# Switch.net
KiCad netlist of a schematic drawn in EAGLE
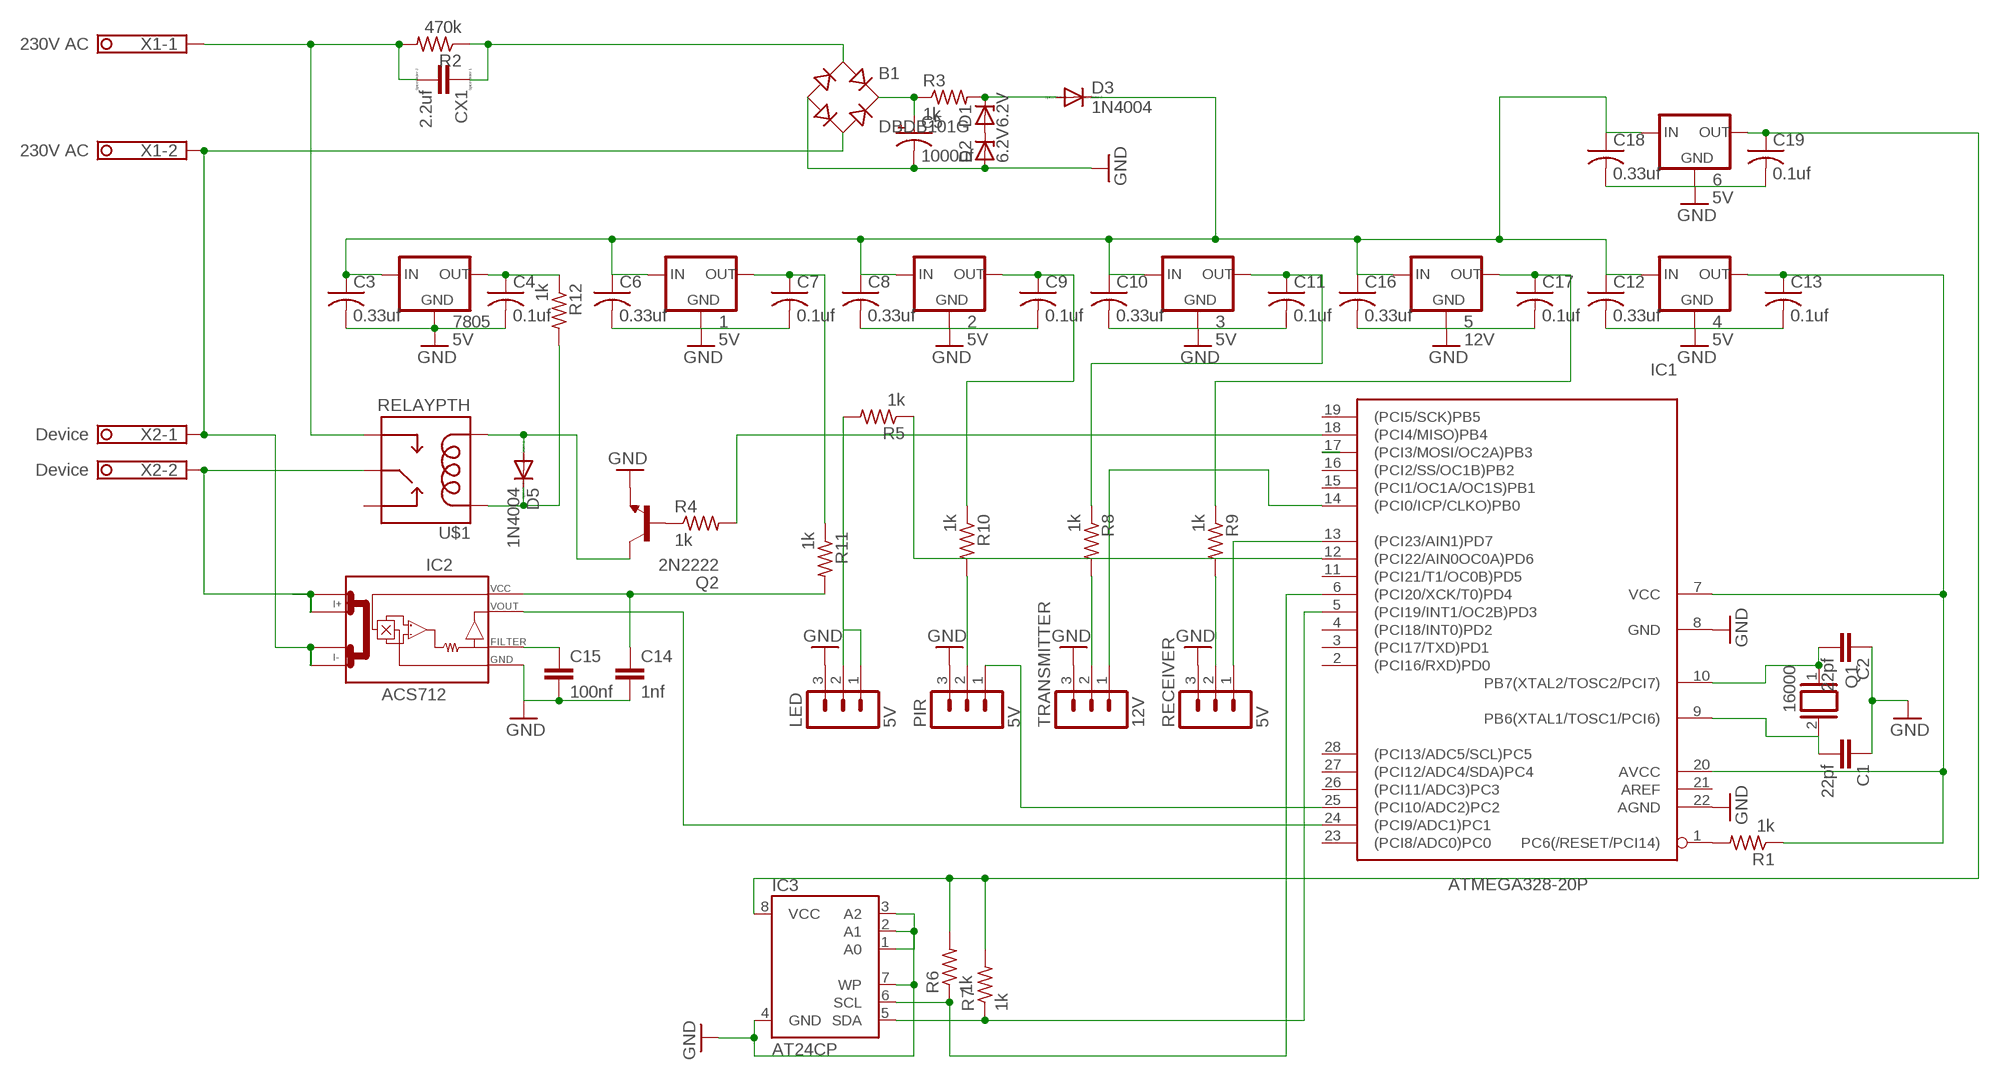
[diagram p0: schematic, sheet 1]

(export (version "E")
  (design (tool "Eeschema 10.0.6"))
  (components
    (comp (ref "1")
      (value "5V")
      (footprint "eagle-import:78XXL")
      (libsource (lib "eagle-import") (part "78XXL"))
    )
    (comp (ref "2")
      (value "5V")
      (footprint "eagle-import:78XXL")
      (libsource (lib "eagle-import") (part "78XXL"))
    )
    (comp (ref "3")
      (value "5V")
      (footprint "eagle-import:78XXL")
      (libsource (lib "eagle-import") (part "78XXL"))
    )
    (comp (ref "4")
      (value "5V")
      (footprint "eagle-import:78XXL")
      (libsource (lib "eagle-import") (part "78XXL"))
    )
    (comp (ref "5")
      (value "12V")
      (footprint "eagle-import:78XXL")
      (libsource (lib "eagle-import") (part "78XXL"))
    )
    (comp (ref "6")
      (value "5V")
      (footprint "eagle-import:78XXL")
      (libsource (lib "eagle-import") (part "78XXL"))
    )
    (comp (ref "7805")
      (value "5V")
      (footprint "eagle-import:78XXL")
      (libsource (lib "eagle-import") (part "78XXL"))
    )
    (comp (ref "B1")
      (value "DBDB101G")
      (footprint "eagle-import:DB")
      (libsource (lib "eagle-import") (part "DB?GDB101"))
    )
    (comp (ref "C1")
      (value "22pf")
      (footprint "eagle-import:C050-030X075")
      (libsource (lib "eagle-import") (part "C-EU050-030X075"))
    )
    (comp (ref "C2")
      (value "22pf")
      (footprint "eagle-import:C050-030X075")
      (libsource (lib "eagle-import") (part "C-EU050-030X075"))
    )
    (comp (ref "C3")
      (value "0.33uf")
      (footprint "eagle-import:C025-024X044")
      (libsource (lib "eagle-import") (part "C-US025-024X044"))
    )
    (comp (ref "C4")
      (value "0.1uf")
      (footprint "eagle-import:C025-024X044")
      (libsource (lib "eagle-import") (part "C-US025-024X044"))
    )
    (comp (ref "C5")
      (value "1000uf")
      (footprint "eagle-import:E2,5-7")
      (libsource (lib "eagle-import") (part "CPOL-USE2.5-7"))
    )
    (comp (ref "C6")
      (value "0.33uf")
      (footprint "eagle-import:C025-024X044")
      (libsource (lib "eagle-import") (part "C-US025-024X044"))
    )
    (comp (ref "C7")
      (value "0.1uf")
      (footprint "eagle-import:C025-024X044")
      (libsource (lib "eagle-import") (part "C-US025-024X044"))
    )
    (comp (ref "C8")
      (value "0.33uf")
      (footprint "eagle-import:C025-024X044")
      (libsource (lib "eagle-import") (part "C-US025-024X044"))
    )
    (comp (ref "C9")
      (value "0.1uf")
      (footprint "eagle-import:C025-024X044")
      (libsource (lib "eagle-import") (part "C-US025-024X044"))
    )
    (comp (ref "C10")
      (value "0.33uf")
      (footprint "eagle-import:C025-024X044")
      (libsource (lib "eagle-import") (part "C-US025-024X044"))
    )
    (comp (ref "C11")
      (value "0.1uf")
      (footprint "eagle-import:C025-024X044")
      (libsource (lib "eagle-import") (part "C-US025-024X044"))
    )
    (comp (ref "C12")
      (value "0.33uf")
      (footprint "eagle-import:C025-024X044")
      (libsource (lib "eagle-import") (part "C-US025-024X044"))
    )
    (comp (ref "C13")
      (value "0.1uf")
      (footprint "eagle-import:C025-024X044")
      (libsource (lib "eagle-import") (part "C-US025-024X044"))
    )
    (comp (ref "C14")
      (value "1nf")
      (footprint "eagle-import:C050-025X075")
      (libsource (lib "eagle-import") (part "C-EU050-025X075"))
    )
    (comp (ref "C15")
      (value "100nf")
      (footprint "eagle-import:C050-024X044")
      (libsource (lib "eagle-import") (part "C-EU050-024X044"))
    )
    (comp (ref "C16")
      (value "0.33uf")
      (footprint "eagle-import:C025-024X044")
      (libsource (lib "eagle-import") (part "C-US025-024X044"))
    )
    (comp (ref "C17")
      (value "0.1uf")
      (footprint "eagle-import:C025-024X044")
      (libsource (lib "eagle-import") (part "C-US025-024X044"))
    )
    (comp (ref "C18")
      (value "0.33uf")
      (footprint "eagle-import:C025-024X044")
      (libsource (lib "eagle-import") (part "C-US025-024X044"))
    )
    (comp (ref "C19")
      (value "0.1uf")
      (footprint "eagle-import:C025-024X044")
      (libsource (lib "eagle-import") (part "C-US025-024X044"))
    )
    (comp (ref "CX1")
      (value "2.2uf")
      (footprint "eagle-import:XC15B6")
      (libsource (lib "eagle-import") (part "CXXC15B6"))
    )
    (comp (ref "D1")
      (value "6.2V")
      (footprint "eagle-import:DO35Z10")
      (libsource (lib "eagle-import") (part "ZENER-DIODEDO35Z10"))
    )
    (comp (ref "D2")
      (value "6.2V")
      (footprint "eagle-import:DO35Z10")
      (libsource (lib "eagle-import") (part "ZENER-DIODEDO35Z10"))
    )
    (comp (ref "D3")
      (value "1N4004")
      (footprint "eagle-import:DO41-10")
      (libsource (lib "eagle-import") (part "1N4004"))
    )
    (comp (ref "D5")
      (value "1N4004")
      (footprint "eagle-import:DO41-10")
      (libsource (lib "eagle-import") (part "1N4004"))
    )
    (comp (ref "IC1")
      (value "ATMEGA328-20P")
      (footprint "eagle-import:DIL28-3")
      (libsource (lib "eagle-import") (part "ATMEGA328P-20"))
    )
    (comp (ref "IC2")
      (value "ACS712")
      (footprint "eagle-import:SO08")
      (libsource (lib "eagle-import") (part "ACS712"))
    )
    (comp (ref "IC3")
      (value "AT24CP")
      (footprint "eagle-import:DIL08")
      (fields (field (name "MPN") "AT24C1024BW-SH-B"))
      (libsource (lib "eagle-import") (part "AT24CP"))
    )
    (comp (ref "LED")
      (value "5V")
      (footprint "eagle-import:MA03-1")
      (libsource (lib "eagle-import") (part "MA03-1"))
    )
    (comp (ref "PIR")
      (value "5V")
      (footprint "eagle-import:MA03-1")
      (libsource (lib "eagle-import") (part "MA03-1"))
    )
    (comp (ref "Q1")
      (value "16000")
      (footprint "eagle-import:QS")
      (libsource (lib "eagle-import") (part "XTAL/S"))
    )
    (comp (ref "Q2")
      (value "2N2222")
      (footprint "eagle-import:TO18")
      (libsource (lib "eagle-import") (part "2N2222"))
    )
    (comp (ref "R1")
      (value "1k")
      (footprint "eagle-import:0207_10")
      (libsource (lib "eagle-import") (part "R-US_0207/10"))
    )
    (comp (ref "R2")
      (value "470k")
      (footprint "eagle-import:0207_12")
      (libsource (lib "eagle-import") (part "R-US_0207/12"))
    )
    (comp (ref "R3")
      (value "1k")
      (footprint "eagle-import:0207_12")
      (libsource (lib "eagle-import") (part "R-US_0207/12"))
    )
    (comp (ref "R4")
      (value "1k")
      (footprint "eagle-import:0207_10")
      (libsource (lib "eagle-import") (part "R-US_0207/10"))
    )
    (comp (ref "R5")
      (value "1k")
      (footprint "eagle-import:0207_10")
      (libsource (lib "eagle-import") (part "R-US_0207/10"))
    )
    (comp (ref "R6")
      (value "1k")
      (footprint "eagle-import:0207_10")
      (libsource (lib "eagle-import") (part "R-US_0207/10"))
    )
    (comp (ref "R7")
      (value "1k")
      (footprint "eagle-import:0207_10")
      (libsource (lib "eagle-import") (part "R-US_0207/10"))
    )
    (comp (ref "R8")
      (value "1k")
      (footprint "eagle-import:0207_10")
      (libsource (lib "eagle-import") (part "R-US_0207/10"))
    )
    (comp (ref "R9")
      (value "1k")
      (footprint "eagle-import:0207_10")
      (libsource (lib "eagle-import") (part "R-US_0207/10"))
    )
    (comp (ref "R10")
      (value "1k")
      (footprint "eagle-import:0207_10")
      (libsource (lib "eagle-import") (part "R-US_0207/10"))
    )
    (comp (ref "R11")
      (value "1k")
      (footprint "eagle-import:0207_10")
      (libsource (lib "eagle-import") (part "R-US_0207/10"))
    )
    (comp (ref "R12")
      (value "1k")
      (footprint "eagle-import:0207_10")
      (libsource (lib "eagle-import") (part "R-US_0207/10"))
    )
    (comp (ref "RECEIVER")
      (value "5V")
      (footprint "eagle-import:MA03-1")
      (libsource (lib "eagle-import") (part "MA03-1"))
    )
    (comp (ref "TRANSMITTER")
      (value "12V")
      (footprint "eagle-import:MA03-1")
      (libsource (lib "eagle-import") (part "MA03-1"))
    )
    (comp (ref "U$1")
      (value "RELAYPTH")
      (footprint "eagle-import:SRD-05VDC-SL-C")
      (libsource (lib "eagle-import") (part "RELAYPTH"))
    )
    (comp (ref "X1")
      (value "230V AC")
      (footprint "eagle-import:1751248")
      (libsource (lib "eagle-import") (part "1751248"))
    )
    (comp (ref "X2")
      (value "Device")
      (footprint "eagle-import:1751248")
      (libsource (lib "eagle-import") (part "1751248"))
    )
  )
  (nets
    (net (code "1") (name "GND") (class "Default")
      (node (ref "1") (pin "GND") (pinfunction "GND_GND") (pintype "input"))
      (node (ref "2") (pin "GND") (pinfunction "GND_GND") (pintype "input"))
      (node (ref "3") (pin "GND") (pinfunction "GND_GND") (pintype "input"))
      (node (ref "4") (pin "GND") (pinfunction "GND_GND") (pintype "input"))
      (node (ref "5") (pin "GND") (pinfunction "GND_GND") (pintype "input"))
      (node (ref "6") (pin "GND") (pinfunction "GND_GND") (pintype "input"))
      (node (ref "7805") (pin "GND") (pinfunction "GND_GND") (pintype "input"))
      (node (ref "B1") (pin "-") (pinfunction "-_-") (pintype "passive"))
      (node (ref "C1") (pin "1") (pinfunction "1_1") (pintype "passive"))
      (node (ref "C10") (pin "2") (pinfunction "2_2") (pintype "passive"))
      (node (ref "C11") (pin "2") (pinfunction "2_2") (pintype "passive"))
      (node (ref "C12") (pin "2") (pinfunction "2_2") (pintype "passive"))
      (node (ref "C13") (pin "2") (pinfunction "2_2") (pintype "passive"))
      (node (ref "C14") (pin "2") (pinfunction "2_2") (pintype "passive"))
      (node (ref "C15") (pin "2") (pinfunction "2_2") (pintype "passive"))
      (node (ref "C16") (pin "2") (pinfunction "2_2") (pintype "passive"))
      (node (ref "C17") (pin "2") (pinfunction "2_2") (pintype "passive"))
      (node (ref "C18") (pin "2") (pinfunction "2_2") (pintype "passive"))
      (node (ref "C19") (pin "2") (pinfunction "2_2") (pintype "passive"))
      (node (ref "C2") (pin "1") (pinfunction "1_1") (pintype "passive"))
      (node (ref "C3") (pin "2") (pinfunction "2_2") (pintype "passive"))
      (node (ref "C4") (pin "2") (pinfunction "2_2") (pintype "passive"))
      (node (ref "C5") (pin "-") (pinfunction "-_-") (pintype "passive"))
      (node (ref "C6") (pin "2") (pinfunction "2_2") (pintype "passive"))
      (node (ref "C7") (pin "2") (pinfunction "2_2") (pintype "passive"))
      (node (ref "C8") (pin "2") (pinfunction "2_2") (pintype "passive"))
      (node (ref "C9") (pin "2") (pinfunction "2_2") (pintype "passive"))
      (node (ref "D2") (pin "A") (pinfunction "A_A") (pintype "passive"))
      (node (ref "IC1") (pin "22") (pinfunction "AGND_22") (pintype "bidirectional"))
      (node (ref "IC1") (pin "8") (pinfunction "GND_8") (pintype "bidirectional"))
      (node (ref "IC2") (pin "5") (pinfunction "GND_5") (pintype "power_in"))
      (node (ref "IC3") (pin "1") (pinfunction "A0_1") (pintype "input"))
      (node (ref "IC3") (pin "2") (pinfunction "A1_2") (pintype "input"))
      (node (ref "IC3") (pin "3") (pinfunction "A2_3") (pintype "input"))
      (node (ref "IC3") (pin "4") (pinfunction "GND_4") (pintype "power_in"))
      (node (ref "IC3") (pin "7") (pinfunction "WP_7") (pintype "input"))
      (node (ref "LED") (pin "3") (pinfunction "3_3") (pintype "passive"))
      (node (ref "PIR") (pin "3") (pinfunction "3_3") (pintype "passive"))
      (node (ref "Q2") (pin "1") (pinfunction "E_1") (pintype "passive"))
      (node (ref "RECEIVER") (pin "3") (pinfunction "3_3") (pintype "passive"))
      (node (ref "TRANSMITTER") (pin "3") (pinfunction "3_3") (pintype "passive"))
    )
    (net (code "2") (name "Net-(1-PadIN)") (class "Default")
      (node (ref "1") (pin "IN") (pinfunction "IN_IN") (pintype "input"))
      (node (ref "2") (pin "IN") (pinfunction "IN_IN") (pintype "input"))
      (node (ref "3") (pin "IN") (pinfunction "IN_IN") (pintype "input"))
      (node (ref "4") (pin "IN") (pinfunction "IN_IN") (pintype "input"))
      (node (ref "5") (pin "IN") (pinfunction "IN_IN") (pintype "input"))
      (node (ref "6") (pin "IN") (pinfunction "IN_IN") (pintype "input"))
      (node (ref "7805") (pin "IN") (pinfunction "IN_IN") (pintype "input"))
      (node (ref "C10") (pin "1") (pinfunction "1_1") (pintype "passive"))
      (node (ref "C12") (pin "1") (pinfunction "1_1") (pintype "passive"))
      (node (ref "C16") (pin "1") (pinfunction "1_1") (pintype "passive"))
      (node (ref "C18") (pin "1") (pinfunction "1_1") (pintype "passive"))
      (node (ref "C3") (pin "1") (pinfunction "1_1") (pintype "passive"))
      (node (ref "C6") (pin "1") (pinfunction "1_1") (pintype "passive"))
      (node (ref "C8") (pin "1") (pinfunction "1_1") (pintype "passive"))
      (node (ref "D3") (pin "C") (pinfunction "C_C") (pintype "passive"))
    )
    (net (code "3") (name "Net-(1-PadOUT)") (class "Default")
      (node (ref "1") (pin "OUT") (pinfunction "OUT_OUT") (pintype "passive"))
      (node (ref "C7") (pin "1") (pinfunction "1_1") (pintype "passive"))
      (node (ref "R11") (pin "1") (pinfunction "1_1") (pintype "passive"))
    )
    (net (code "4") (name "Net-(2-PadOUT)") (class "Default")
      (node (ref "2") (pin "OUT") (pinfunction "OUT_OUT") (pintype "passive"))
      (node (ref "C9") (pin "1") (pinfunction "1_1") (pintype "passive"))
      (node (ref "R10") (pin "1") (pinfunction "1_1") (pintype "passive"))
    )
    (net (code "5") (name "Net-(3-PadOUT)") (class "Default")
      (node (ref "3") (pin "OUT") (pinfunction "OUT_OUT") (pintype "passive"))
      (node (ref "C11") (pin "1") (pinfunction "1_1") (pintype "passive"))
      (node (ref "R8") (pin "1") (pinfunction "1_1") (pintype "passive"))
    )
    (net (code "6") (name "Net-(5-PadOUT)") (class "Default")
      (node (ref "5") (pin "OUT") (pinfunction "OUT_OUT") (pintype "passive"))
      (node (ref "C17") (pin "1") (pinfunction "1_1") (pintype "passive"))
      (node (ref "R9") (pin "1") (pinfunction "1_1") (pintype "passive"))
    )
    (net (code "7") (name "Net-(7805-PadOUT)") (class "Default")
      (node (ref "7805") (pin "OUT") (pinfunction "OUT_OUT") (pintype "passive"))
      (node (ref "C4") (pin "1") (pinfunction "1_1") (pintype "passive"))
      (node (ref "R12") (pin "1") (pinfunction "1_1") (pintype "passive"))
    )
    (net (code "8") (name "Net-(B1-Pad+)") (class "Default")
      (node (ref "B1") (pin "+") (pinfunction "+_+") (pintype "passive"))
      (node (ref "C5") (pin "+") (pinfunction "+_+") (pintype "passive"))
      (node (ref "R3") (pin "1") (pinfunction "1_1") (pintype "passive"))
    )
    (net (code "9") (name "Net-(B1-PadAC1)") (class "Default")
      (node (ref "B1") (pin "AC1") (pinfunction "AC1_AC1") (pintype "passive"))
      (node (ref "CX1") (pin "1") (pinfunction "1_1") (pintype "passive"))
      (node (ref "R2") (pin "1") (pinfunction "1_1") (pintype "passive"))
    )
    (net (code "10") (name "Net-(D1-PadA)") (class "Default")
      (node (ref "D1") (pin "A") (pinfunction "A_A") (pintype "passive"))
      (node (ref "D2") (pin "C") (pinfunction "C_C") (pintype "passive"))
    )
    (net (code "11") (name "Net-(D1-PadC)") (class "Default")
      (node (ref "D1") (pin "C") (pinfunction "C_C") (pintype "passive"))
      (node (ref "D3") (pin "A") (pinfunction "A_A") (pintype "passive"))
      (node (ref "R3") (pin "2") (pinfunction "2_2") (pintype "passive"))
    )
    (net (code "12") (name "Net-(D5-PadC)") (class "Default")
      (node (ref "D5") (pin "C") (pinfunction "C_C") (pintype "passive"))
      (node (ref "R12") (pin "2") (pinfunction "2_2") (pintype "passive"))
      (node (ref "U$1") (pin "COIL1") (pinfunction "COIL1_COIL1") (pintype "bidirectional"))
    )
    (net (code "13") (name "Net-(IC1-(PCI0{slash}ICP{slash}CLKO)PB0)") (class "Default")
      (node (ref "IC1") (pin "14") (pinfunction "(PCI0/ICP/CLKO)PB0_14") (pintype "bidirectional"))
      (node (ref "TRANSMITTER") (pin "1") (pinfunction "1_1") (pintype "passive"))
    )
    (net (code "14") (name "Net-(IC1-(PCI4{slash}MISO)PB4)") (class "Default")
      (node (ref "IC1") (pin "18") (pinfunction "(PCI4/MISO)PB4_18") (pintype "bidirectional"))
      (node (ref "R4") (pin "2") (pinfunction "2_2") (pintype "passive"))
    )
    (net (code "15") (name "Net-(IC1-(PCI9{slash}ADC1)PC1)") (class "Default")
      (node (ref "IC1") (pin "24") (pinfunction "(PCI9/ADC1)PC1_24") (pintype "bidirectional"))
      (node (ref "IC2") (pin "7") (pinfunction "VOUT_7") (pintype "output"))
    )
    (net (code "16") (name "Net-(IC1-(PCI10{slash}ADC2)PC2)") (class "Default")
      (node (ref "IC1") (pin "25") (pinfunction "(PCI10/ADC2)PC2_25") (pintype "bidirectional"))
      (node (ref "PIR") (pin "1") (pinfunction "1_1") (pintype "passive"))
    )
    (net (code "17") (name "Net-(IC1-(PCI19{slash}INT1{slash}OC2B)PD3)") (class "Default")
      (node (ref "IC1") (pin "5") (pinfunction "(PCI19/INT1/OC2B)PD3_5") (pintype "bidirectional"))
      (node (ref "IC3") (pin "5") (pinfunction "SDA_5") (pintype "bidirectional"))
      (node (ref "R7") (pin "1") (pinfunction "1_1") (pintype "passive"))
    )
    (net (code "18") (name "Net-(IC1-(PCI20{slash}XCK{slash}T0)PD4)") (class "Default")
      (node (ref "IC1") (pin "6") (pinfunction "(PCI20/XCK/T0)PD4_6") (pintype "bidirectional"))
      (node (ref "IC3") (pin "6") (pinfunction "SCL_6") (pintype "bidirectional"))
      (node (ref "R6") (pin "1") (pinfunction "1_1") (pintype "passive"))
    )
    (net (code "19") (name "Net-(IC1-(PCI22{slash}AIN0OC0A)PD6)") (class "Default")
      (node (ref "IC1") (pin "12") (pinfunction "(PCI22/AIN0OC0A)PD6_12") (pintype "bidirectional"))
      (node (ref "R5") (pin "1") (pinfunction "1_1") (pintype "passive"))
    )
    (net (code "20") (name "Net-(IC1-(PCI23{slash}AIN1)PD7)") (class "Default")
      (node (ref "IC1") (pin "13") (pinfunction "(PCI23/AIN1)PD7_13") (pintype "bidirectional"))
      (node (ref "RECEIVER") (pin "1") (pinfunction "1_1") (pintype "passive"))
    )
    (net (code "21") (name "Net-(IC1-AVCC)") (class "Default")
      (node (ref "4") (pin "OUT") (pinfunction "OUT_OUT") (pintype "passive"))
      (node (ref "C13") (pin "1") (pinfunction "1_1") (pintype "passive"))
      (node (ref "IC1") (pin "20") (pinfunction "AVCC_20") (pintype "bidirectional"))
      (node (ref "IC1") (pin "7") (pinfunction "VCC_7") (pintype "bidirectional"))
      (node (ref "R1") (pin "1") (pinfunction "1_1") (pintype "passive"))
    )
    (net (code "22") (name "Net-(IC1-PB6(XTAL1{slash}TOSC1{slash}PCI6))") (class "Default")
      (node (ref "C1") (pin "2") (pinfunction "2_2") (pintype "passive"))
      (node (ref "IC1") (pin "9") (pinfunction "PB6(XTAL1/TOSC1/PCI6)_9") (pintype "bidirectional"))
      (node (ref "Q1") (pin "2") (pinfunction "2_2") (pintype "passive"))
    )
    (net (code "23") (name "Net-(IC1-PB7(XTAL2{slash}TOSC2{slash}PCI7))") (class "Default")
      (node (ref "C2") (pin "2") (pinfunction "2_2") (pintype "passive"))
      (node (ref "IC1") (pin "10") (pinfunction "PB7(XTAL2/TOSC2/PCI7)_10") (pintype "bidirectional"))
      (node (ref "Q1") (pin "1") (pinfunction "1_1") (pintype "passive"))
    )
    (net (code "24") (name "Net-(IC1-PC6({slash}RESET{slash}PCI14))") (class "Default")
      (node (ref "IC1") (pin "1") (pinfunction "PC6(/RESET/PCI14)_1") (pintype "bidirectional"))
      (node (ref "R1") (pin "2") (pinfunction "2_2") (pintype "passive"))
    )
    (net (code "25") (name "Net-(IC2-FILTER)") (class "Default")
      (node (ref "C15") (pin "1") (pinfunction "1_1") (pintype "passive"))
      (node (ref "IC2") (pin "6") (pinfunction "FILTER_6") (pintype "bidirectional"))
    )
    (net (code "26") (name "Net-(IC2-I+_0)") (class "Default")
      (node (ref "IC2") (pin "1") (pinfunction "I+_0_1") (pintype "bidirectional"))
      (node (ref "IC2") (pin "2") (pinfunction "I+_1_2") (pintype "bidirectional"))
      (node (ref "U$1") (pin "SWCOMMON") (pinfunction "SWCOMMON_SWCOMMON") (pintype "bidirectional"))
      (node (ref "X2") (pin "2") (pinfunction "K_2") (pintype "passive"))
    )
    (net (code "27") (name "Net-(IC2-I-_0)") (class "Default")
      (node (ref "B1") (pin "AC2") (pinfunction "AC2_AC2") (pintype "passive"))
      (node (ref "IC2") (pin "3") (pinfunction "I-_0_3") (pintype "bidirectional"))
      (node (ref "IC2") (pin "4") (pinfunction "I-_1_4") (pintype "bidirectional"))
      (node (ref "X1") (pin "2") (pinfunction "K_2") (pintype "passive"))
      (node (ref "X2") (pin "1") (pinfunction "K_1") (pintype "passive"))
    )
    (net (code "28") (name "Net-(IC2-VCC)") (class "Default")
      (node (ref "C14") (pin "1") (pinfunction "1_1") (pintype "passive"))
      (node (ref "IC2") (pin "8") (pinfunction "VCC_8") (pintype "power_in"))
      (node (ref "R11") (pin "2") (pinfunction "2_2") (pintype "passive"))
    )
    (net (code "29") (name "Net-(IC3-VCC)") (class "Default")
      (node (ref "6") (pin "OUT") (pinfunction "OUT_OUT") (pintype "passive"))
      (node (ref "C19") (pin "1") (pinfunction "1_1") (pintype "passive"))
      (node (ref "IC3") (pin "8") (pinfunction "VCC_8") (pintype "power_in"))
      (node (ref "R6") (pin "2") (pinfunction "2_2") (pintype "passive"))
      (node (ref "R7") (pin "2") (pinfunction "2_2") (pintype "passive"))
    )
    (net (code "30") (name "Net-(LED-Pad1)") (class "Default")
      (node (ref "LED") (pin "1") (pinfunction "1_1") (pintype "passive"))
      (node (ref "LED") (pin "2") (pinfunction "2_2") (pintype "passive"))
      (node (ref "R5") (pin "2") (pinfunction "2_2") (pintype "passive"))
    )
    (net (code "31") (name "Net-(PIR-Pad2)") (class "Default")
      (node (ref "PIR") (pin "2") (pinfunction "2_2") (pintype "passive"))
      (node (ref "R10") (pin "2") (pinfunction "2_2") (pintype "passive"))
    )
    (net (code "32") (name "Net-(Q2-B)") (class "Default")
      (node (ref "Q2") (pin "2") (pinfunction "B_2") (pintype "passive"))
      (node (ref "R4") (pin "1") (pinfunction "1_1") (pintype "passive"))
    )
    (net (code "33") (name "Net-(Q2-C)") (class "Default")
      (node (ref "D5") (pin "A") (pinfunction "A_A") (pintype "passive"))
      (node (ref "Q2") (pin "3") (pinfunction "C_3") (pintype "passive"))
      (node (ref "U$1") (pin "COIL0") (pinfunction "COIL0_COIL0") (pintype "bidirectional"))
    )
    (net (code "34") (name "Net-(R8-Pad2)") (class "Default")
      (node (ref "R8") (pin "2") (pinfunction "2_2") (pintype "passive"))
      (node (ref "TRANSMITTER") (pin "2") (pinfunction "2_2") (pintype "passive"))
    )
    (net (code "35") (name "Net-(R9-Pad2)") (class "Default")
      (node (ref "R9") (pin "2") (pinfunction "2_2") (pintype "passive"))
      (node (ref "RECEIVER") (pin "2") (pinfunction "2_2") (pintype "passive"))
    )
    (net (code "36") (name "Net-(X1A-K)") (class "Default")
      (node (ref "CX1") (pin "2") (pinfunction "2_2") (pintype "passive"))
      (node (ref "R2") (pin "2") (pinfunction "2_2") (pintype "passive"))
      (node (ref "U$1") (pin "SWOPEN") (pinfunction "SWOPEN_SWOPEN") (pintype "bidirectional"))
      (node (ref "X1") (pin "1") (pinfunction "K_1") (pintype "passive"))
    )
    (net (code "37") (name "unconnected-(IC1-(PCI1{slash}OC1A{slash}OC1S)PB1-Pad15)") (class "Default")
      (node (ref "IC1") (pin "15") (pinfunction "(PCI1/OC1A/OC1S)PB1_15") (pintype "bidirectional"))
    )
    (net (code "38") (name "unconnected-(IC1-(PCI2{slash}SS{slash}OC1B)PB2-Pad16)") (class "Default")
      (node (ref "IC1") (pin "16") (pinfunction "(PCI2/SS/OC1B)PB2_16") (pintype "bidirectional"))
    )
    (net (code "39") (name "unconnected-(IC1-(PCI3{slash}MOSI{slash}OC2A)PB3-Pad17)") (class "Default")
      (node (ref "IC1") (pin "17") (pinfunction "(PCI3/MOSI/OC2A)PB3_17") (pintype "bidirectional"))
    )
    (net (code "40") (name "unconnected-(IC1-(PCI5{slash}SCK)PB5-Pad19)") (class "Default")
      (node (ref "IC1") (pin "19") (pinfunction "(PCI5/SCK)PB5_19") (pintype "bidirectional"))
    )
    (net (code "41") (name "unconnected-(IC1-(PCI8{slash}ADC0)PC0-Pad23)") (class "Default")
      (node (ref "IC1") (pin "23") (pinfunction "(PCI8/ADC0)PC0_23") (pintype "bidirectional"))
    )
    (net (code "42") (name "unconnected-(IC1-(PCI11{slash}ADC3)PC3-Pad26)") (class "Default")
      (node (ref "IC1") (pin "26") (pinfunction "(PCI11/ADC3)PC3_26") (pintype "bidirectional"))
    )
    (net (code "43") (name "unconnected-(IC1-(PCI12{slash}ADC4{slash}SDA)PC4-Pad27)") (class "Default")
      (node (ref "IC1") (pin "27") (pinfunction "(PCI12/ADC4/SDA)PC4_27") (pintype "bidirectional"))
    )
    (net (code "44") (name "unconnected-(IC1-(PCI13{slash}ADC5{slash}SCL)PC5-Pad28)") (class "Default")
      (node (ref "IC1") (pin "28") (pinfunction "(PCI13/ADC5/SCL)PC5_28") (pintype "bidirectional"))
    )
    (net (code "45") (name "unconnected-(IC1-(PCI16{slash}RXD)PD0-Pad2)") (class "Default")
      (node (ref "IC1") (pin "2") (pinfunction "(PCI16/RXD)PD0_2") (pintype "bidirectional"))
    )
    (net (code "46") (name "unconnected-(IC1-(PCI17{slash}TXD)PD1-Pad3)") (class "Default")
      (node (ref "IC1") (pin "3") (pinfunction "(PCI17/TXD)PD1_3") (pintype "bidirectional"))
    )
    (net (code "47") (name "unconnected-(IC1-(PCI18{slash}INT0)PD2-Pad4)") (class "Default")
      (node (ref "IC1") (pin "4") (pinfunction "(PCI18/INT0)PD2_4") (pintype "bidirectional"))
    )
    (net (code "48") (name "unconnected-(IC1-(PCI21{slash}T1{slash}OC0B)PD5-Pad11)") (class "Default")
      (node (ref "IC1") (pin "11") (pinfunction "(PCI21/T1/OC0B)PD5_11") (pintype "bidirectional"))
    )
    (net (code "49") (name "unconnected-(IC1-AREF-Pad21)") (class "Default")
      (node (ref "IC1") (pin "21") (pinfunction "AREF_21") (pintype "bidirectional"))
    )
    (net (code "50") (name "unconnected-(U$1-SWCLOSE-PadSWCLOSED)") (class "Default")
      (node (ref "U$1") (pin "SWCLOSED") (pinfunction "SWCLOSE_SWCLOSED") (pintype "bidirectional"))
    )
  )
)
